# o_clone_rev_a.net
KiCad netlist of a schematic drawn in EAGLE
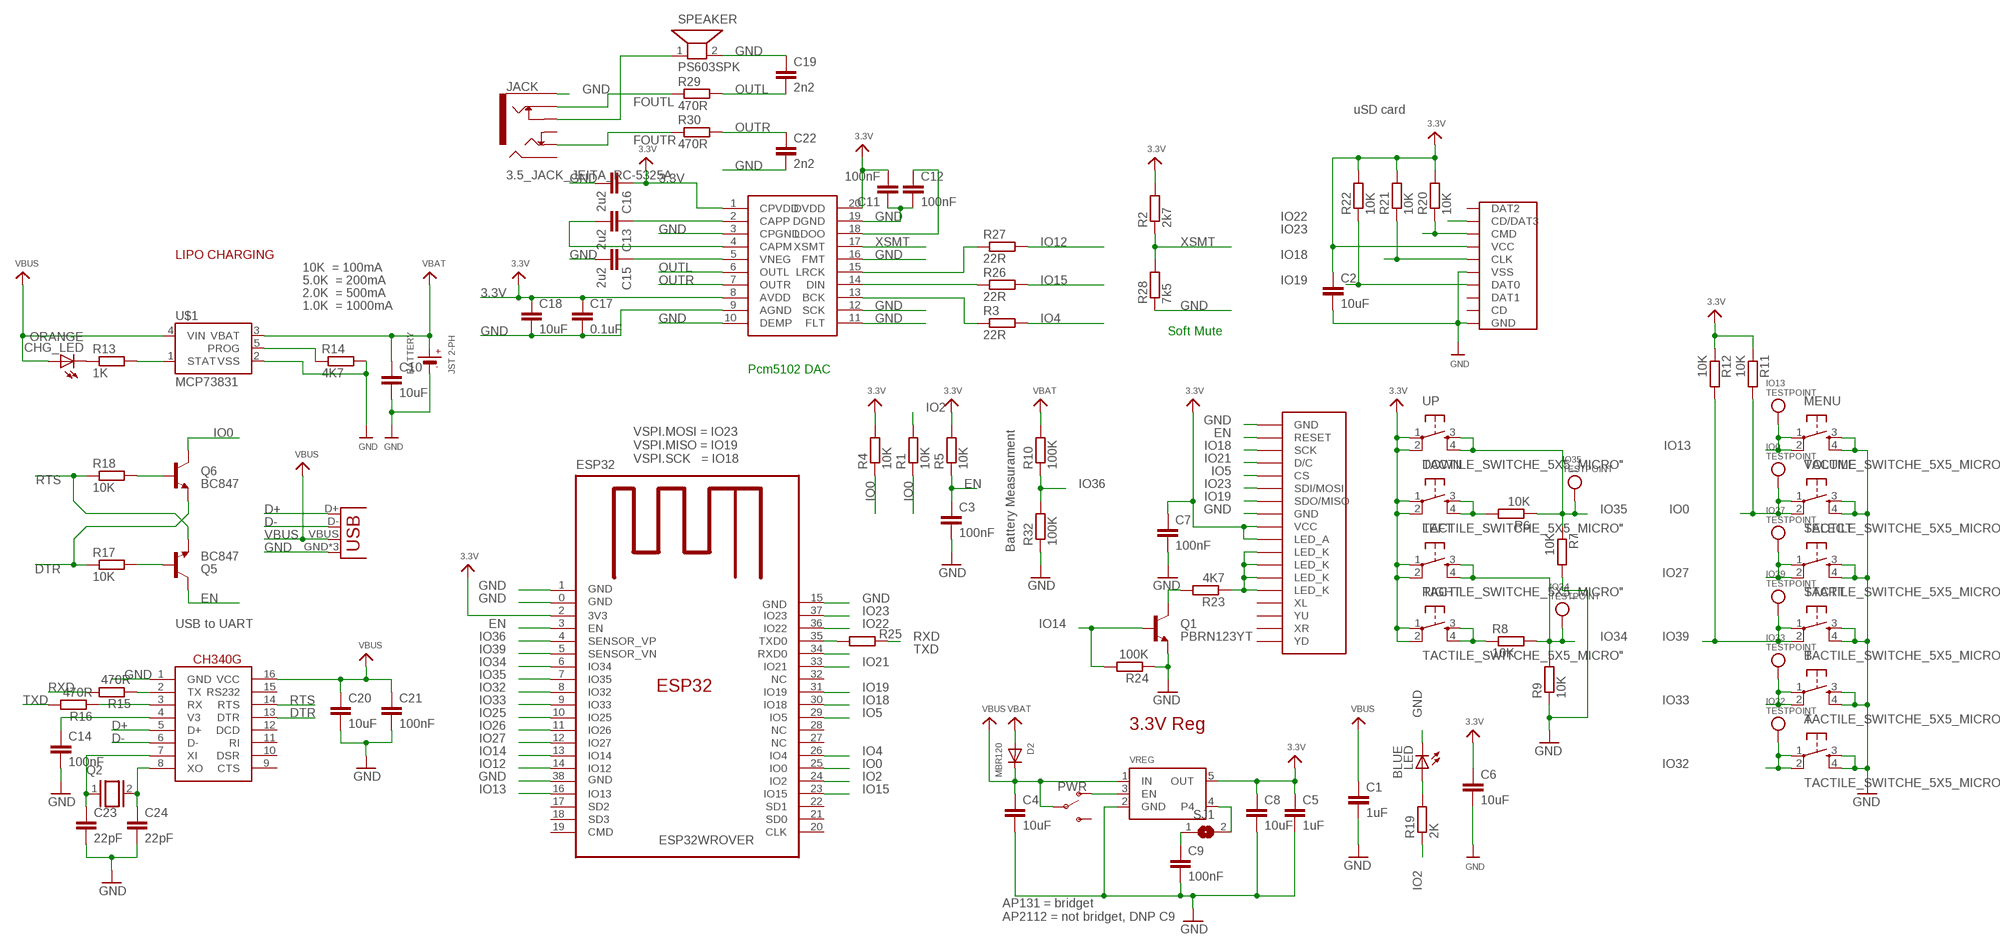
[diagram p0: schematic, sheet 1]

(export (version "E")
  (design (tool "Eeschema 10.0.6"))
  (components
    (comp (ref "A")
      (value "TACTILE_SWITCHE_5X5_MICRO\"")
      (footprint "eagle-import:TACTILE_SWITCH_5X5_MICRO")
      (libsource (lib "eagle-import") (part "TACTILE_SWITCHE_5X5_MICRO{dblquote}"))
    )
    (comp (ref "B")
      (value "TACTILE_SWITCHE_5X5_MICRO\"")
      (footprint "eagle-import:TACTILE_SWITCH_5X5_MICRO")
      (libsource (lib "eagle-import") (part "TACTILE_SWITCHE_5X5_MICRO{dblquote}"))
    )
    (comp (ref "BATTERY")
      (value "JST 2-PH")
      (footprint "eagle-import:JSTPH2")
      (libsource (lib "eagle-import") (part "JST_CONNECTOR"))
    )
    (comp (ref "C1")
      (value "1uF")
      (footprint "eagle-import:C0805")
      (libsource (lib "eagle-import") (part "C-EUC0805"))
    )
    (comp (ref "C2")
      (value "10uF")
      (footprint "eagle-import:C0805")
      (libsource (lib "eagle-import") (part "C-EUC0805"))
    )
    (comp (ref "C3")
      (value "100nF")
      (footprint "eagle-import:C0805")
      (libsource (lib "eagle-import") (part "C-EUC0805"))
    )
    (comp (ref "C4")
      (value "10uF")
      (footprint "eagle-import:C0805")
      (libsource (lib "eagle-import") (part "C-EUC0805"))
    )
    (comp (ref "C5")
      (value "1uF")
      (footprint "eagle-import:C0805")
      (libsource (lib "eagle-import") (part "C-EUC0805"))
    )
    (comp (ref "C6")
      (value "10uF")
      (footprint "eagle-import:C0805")
      (libsource (lib "eagle-import") (part "C-EUC0805"))
    )
    (comp (ref "C7")
      (value "100nF")
      (footprint "eagle-import:C0805")
      (libsource (lib "eagle-import") (part "C-EUC0805"))
    )
    (comp (ref "C8")
      (value "10uF")
      (footprint "eagle-import:C0805")
      (libsource (lib "eagle-import") (part "C-EUC0805"))
    )
    (comp (ref "C9")
      (value "100nF")
      (footprint "eagle-import:C0805")
      (libsource (lib "eagle-import") (part "C-EUC0805"))
    )
    (comp (ref "C10")
      (value "10uF")
      (footprint "eagle-import:C0805")
      (libsource (lib "eagle-import") (part "C-EUC0805"))
    )
    (comp (ref "C11")
      (value "100nF")
      (footprint "eagle-import:C0805")
      (libsource (lib "eagle-import") (part "C-EUC0805"))
    )
    (comp (ref "C12")
      (value "100nF")
      (footprint "eagle-import:C0805")
      (libsource (lib "eagle-import") (part "C-EUC0805"))
    )
    (comp (ref "C13")
      (value "2u2")
      (footprint "eagle-import:C0805")
      (libsource (lib "eagle-import") (part "C-EUC0805"))
    )
    (comp (ref "C14")
      (value "100nF")
      (footprint "eagle-import:C0805")
      (libsource (lib "eagle-import") (part "C-EUC0805"))
    )
    (comp (ref "C15")
      (value "2u2")
      (footprint "eagle-import:C0805")
      (libsource (lib "eagle-import") (part "C-EUC0805"))
    )
    (comp (ref "C16")
      (value "2u2")
      (footprint "eagle-import:C0805")
      (libsource (lib "eagle-import") (part "C-EUC0805"))
    )
    (comp (ref "C17")
      (value "0.1uF")
      (footprint "eagle-import:C0805")
      (libsource (lib "eagle-import") (part "C-EUC0805"))
    )
    (comp (ref "C18")
      (value "10uF")
      (footprint "eagle-import:C0805")
      (libsource (lib "eagle-import") (part "C-EUC0805"))
    )
    (comp (ref "C19")
      (value "2n2")
      (footprint "eagle-import:C0805")
      (libsource (lib "eagle-import") (part "C-EUC0805"))
    )
    (comp (ref "C20")
      (value "10uF")
      (footprint "eagle-import:C0805")
      (libsource (lib "eagle-import") (part "C-EUC0805"))
    )
    (comp (ref "C21")
      (value "100nF")
      (footprint "eagle-import:C0805")
      (libsource (lib "eagle-import") (part "C-EUC0805"))
    )
    (comp (ref "C22")
      (value "2n2")
      (footprint "eagle-import:C0805")
      (libsource (lib "eagle-import") (part "C-EUC0805"))
    )
    (comp (ref "C23")
      (value "22pF")
      (footprint "eagle-import:C0805")
      (libsource (lib "eagle-import") (part "C-EUC0805"))
    )
    (comp (ref "C24")
      (value "22pF")
      (footprint "eagle-import:C0805")
      (libsource (lib "eagle-import") (part "C-EUC0805"))
    )
    (comp (ref "CHG_LED")
      (value "ORANGE")
      (footprint "eagle-import:CHIPLED_0805")
      (libsource (lib "eagle-import") (part "LEDCHIPLED_0805"))
    )
    (comp (ref "D2")
      (value "MBR120")
      (footprint "eagle-import:SOD-123")
      (libsource (lib "eagle-import") (part "DIODESOD-123"))
    )
    (comp (ref "DOWN")
      (value "TACTILE_SWITCHE_5X5_MICRO\"")
      (footprint "eagle-import:TACTILE_SWITCH_5X5_MICRO")
      (libsource (lib "eagle-import") (part "TACTILE_SWITCHE_5X5_MICRO{dblquote}"))
    )
    (comp (ref "ESP32")
      (value "ESP32WROVER")
      (footprint "eagle-import:ESP32WROVER")
      (libsource (lib "eagle-import") (part "ESP32WROVER"))
    )
    (comp (ref "IO0")
      (value "TESTPOINT")
      (footprint "eagle-import:TESTPOINT")
      (libsource (lib "eagle-import") (part "TESTPOINT"))
    )
    (comp (ref "IO13")
      (value "TESTPOINT")
      (footprint "eagle-import:TESTPOINT")
      (libsource (lib "eagle-import") (part "TESTPOINT"))
    )
    (comp (ref "IO27")
      (value "TESTPOINT")
      (footprint "eagle-import:TESTPOINT")
      (libsource (lib "eagle-import") (part "TESTPOINT"))
    )
    (comp (ref "IO32")
      (value "TESTPOINT")
      (footprint "eagle-import:TESTPOINT")
      (libsource (lib "eagle-import") (part "TESTPOINT"))
    )
    (comp (ref "IO33")
      (value "TESTPOINT")
      (footprint "eagle-import:TESTPOINT")
      (libsource (lib "eagle-import") (part "TESTPOINT"))
    )
    (comp (ref "IO34")
      (value "TESTPOINT")
      (footprint "eagle-import:TESTPOINT")
      (libsource (lib "eagle-import") (part "TESTPOINT"))
    )
    (comp (ref "IO35")
      (value "TESTPOINT")
      (footprint "eagle-import:TESTPOINT")
      (libsource (lib "eagle-import") (part "TESTPOINT"))
    )
    (comp (ref "IO39")
      (value "TESTPOINT")
      (footprint "eagle-import:TESTPOINT")
      (libsource (lib "eagle-import") (part "TESTPOINT"))
    )
    (comp (ref "JACK")
      (value "3.5_JACK_JEITA_RC-5325A")
      (footprint "eagle-import:3.5_JACK_JEITA_RC-5325A")
      (libsource (lib "eagle-import") (part "3.5_JACK_JEITA_RC-5325A"))
    )
    (comp (ref "LCD")
      (value "ILI9341_3.2LCD_")
      (footprint "eagle-import:LI9341_3.2LCD")
      (libsource (lib "eagle-import") (part "ILI9341_3.2LCD_"))
    )
    (comp (ref "LED")
      (value "BLUE")
      (footprint "eagle-import:CHIPLED_0805")
      (libsource (lib "eagle-import") (part "LEDCHIPLED_0805"))
    )
    (comp (ref "LEFT")
      (value "TACTILE_SWITCHE_5X5_MICRO\"")
      (footprint "eagle-import:TACTILE_SWITCH_5X5_MICRO")
      (libsource (lib "eagle-import") (part "TACTILE_SWITCHE_5X5_MICRO{dblquote}"))
    )
    (comp (ref "MENU")
      (value "TACTILE_SWITCHE_5X5_MICRO\"")
      (footprint "eagle-import:TACTILE_SWITCH_5X5_MICRO")
      (libsource (lib "eagle-import") (part "TACTILE_SWITCHE_5X5_MICRO{dblquote}"))
    )
    (comp (ref "PCM5102")
      (value "PCM5102")
      (footprint "eagle-import:TSSOP20")
      (libsource (lib "eagle-import") (part "PCM5102"))
    )
    (comp (ref "PWR")
      (value "SWITCH-SPDT-SMD-RIGHT-ANGLE")
      (footprint "eagle-import:SWITCH_SPST_SMD_A")
      (libsource (lib "eagle-import") (part "SWITCH-SPDT-SMD-RIGHT-ANGLE"))
    )
    (comp (ref "Q1")
      (value "PBRN123YT")
      (footprint "eagle-import:SOT23-3")
      (libsource (lib "eagle-import") (part "TRANSISTOR_NPNSOT23-3"))
    )
    (comp (ref "Q2")
      (value "XTAL/S")
      (footprint "eagle-import:QS")
      (libsource (lib "eagle-import") (part "XTAL/S"))
    )
    (comp (ref "Q5")
      (value "BC847")
      (footprint "eagle-import:SOT23-3")
      (libsource (lib "eagle-import") (part "TRANSISTOR_NPNSOT23-3"))
    )
    (comp (ref "Q6")
      (value "BC847")
      (footprint "eagle-import:SOT23-3")
      (libsource (lib "eagle-import") (part "TRANSISTOR_NPNSOT23-3"))
    )
    (comp (ref "R1")
      (value "10K")
      (footprint "eagle-import:R0805")
      (libsource (lib "eagle-import") (part "R-EU_R0805"))
    )
    (comp (ref "R2")
      (value "2k7")
      (footprint "eagle-import:R0805")
      (libsource (lib "eagle-import") (part "R-EU_R0805"))
    )
    (comp (ref "R3")
      (value "22R")
      (footprint "eagle-import:R0805")
      (libsource (lib "eagle-import") (part "R-EU_R0805"))
    )
    (comp (ref "R4")
      (value "10K")
      (footprint "eagle-import:R0805")
      (libsource (lib "eagle-import") (part "R-EU_R0805"))
    )
    (comp (ref "R5")
      (value "10K")
      (footprint "eagle-import:R0805")
      (libsource (lib "eagle-import") (part "R-EU_R0805"))
    )
    (comp (ref "R6")
      (value "10K")
      (footprint "eagle-import:R0805")
      (libsource (lib "eagle-import") (part "R-EU_R0805"))
    )
    (comp (ref "R7")
      (value "10K")
      (footprint "eagle-import:R0805")
      (libsource (lib "eagle-import") (part "R-EU_R0805"))
    )
    (comp (ref "R8")
      (value "10K")
      (footprint "eagle-import:R0805")
      (libsource (lib "eagle-import") (part "R-EU_R0805"))
    )
    (comp (ref "R9")
      (value "10K")
      (footprint "eagle-import:R0805")
      (libsource (lib "eagle-import") (part "R-EU_R0805"))
    )
    (comp (ref "R10")
      (value "100K")
      (footprint "eagle-import:R0805")
      (libsource (lib "eagle-import") (part "R-EU_R0805"))
    )
    (comp (ref "R11")
      (value "10K")
      (footprint "eagle-import:R0805")
      (libsource (lib "eagle-import") (part "R-EU_R0805"))
    )
    (comp (ref "R12")
      (value "10K")
      (footprint "eagle-import:R0805")
      (libsource (lib "eagle-import") (part "R-EU_R0805"))
    )
    (comp (ref "R13")
      (value "1K")
      (footprint "eagle-import:R0805")
      (libsource (lib "eagle-import") (part "R-EU_R0805"))
    )
    (comp (ref "R14")
      (value "4K7")
      (footprint "eagle-import:R0805")
      (libsource (lib "eagle-import") (part "R-EU_R0805"))
    )
    (comp (ref "R15")
      (value "470R")
      (footprint "eagle-import:R0805")
      (libsource (lib "eagle-import") (part "R-EU_R0805"))
    )
    (comp (ref "R16")
      (value "470R")
      (footprint "eagle-import:R0805")
      (libsource (lib "eagle-import") (part "R-EU_R0805"))
    )
    (comp (ref "R17")
      (value "10K")
      (footprint "eagle-import:R0805")
      (libsource (lib "eagle-import") (part "R-EU_R0805"))
    )
    (comp (ref "R18")
      (value "10K")
      (footprint "eagle-import:R0805")
      (libsource (lib "eagle-import") (part "R-EU_R0805"))
    )
    (comp (ref "R19")
      (value "2K")
      (footprint "eagle-import:R0805")
      (libsource (lib "eagle-import") (part "R-EU_R0805"))
    )
    (comp (ref "R20")
      (value "10K")
      (footprint "eagle-import:R0805")
      (libsource (lib "eagle-import") (part "R-EU_R0805"))
    )
    (comp (ref "R21")
      (value "10K")
      (footprint "eagle-import:R0805")
      (libsource (lib "eagle-import") (part "R-EU_R0805"))
    )
    (comp (ref "R22")
      (value "10K")
      (footprint "eagle-import:R0805")
      (libsource (lib "eagle-import") (part "R-EU_R0805"))
    )
    (comp (ref "R23")
      (value "4K7")
      (footprint "eagle-import:R0805")
      (libsource (lib "eagle-import") (part "R-EU_R0805"))
    )
    (comp (ref "R24")
      (value "100K")
      (footprint "eagle-import:R0805")
      (libsource (lib "eagle-import") (part "R-EU_R0805"))
    )
    (comp (ref "R25")
      (value "470R")
      (footprint "eagle-import:R0805")
      (libsource (lib "eagle-import") (part "R-EU_R0805"))
    )
    (comp (ref "R26")
      (value "22R")
      (footprint "eagle-import:R0805")
      (libsource (lib "eagle-import") (part "R-EU_R0805"))
    )
    (comp (ref "R27")
      (value "22R")
      (footprint "eagle-import:R0805")
      (libsource (lib "eagle-import") (part "R-EU_R0805"))
    )
    (comp (ref "R28")
      (value "7k5")
      (footprint "eagle-import:R0805")
      (libsource (lib "eagle-import") (part "R-EU_R0805"))
    )
    (comp (ref "R29")
      (value "470R")
      (footprint "eagle-import:R0805")
      (libsource (lib "eagle-import") (part "R-EU_R0805"))
    )
    (comp (ref "R30")
      (value "470R")
      (footprint "eagle-import:R0805")
      (libsource (lib "eagle-import") (part "R-EU_R0805"))
    )
    (comp (ref "R32")
      (value "100K")
      (footprint "eagle-import:R0805")
      (libsource (lib "eagle-import") (part "R-EU_R0805"))
    )
    (comp (ref "RIGHT")
      (value "TACTILE_SWITCHE_5X5_MICRO\"")
      (footprint "eagle-import:TACTILE_SWITCH_5X5_MICRO")
      (libsource (lib "eagle-import") (part "TACTILE_SWITCHE_5X5_MICRO{dblquote}"))
    )
    (comp (ref "SD_CARD")
      (value "MICRO_SD_CARD\"")
      (footprint "eagle-import:TFP09-2--12B")
      (libsource (lib "eagle-import") (part "MICRO_SD_CARD{dblquote}"))
    )
    (comp (ref "SELECT")
      (value "TACTILE_SWITCHE_5X5_MICRO\"")
      (footprint "eagle-import:TACTILE_SWITCH_5X5_MICRO")
      (libsource (lib "eagle-import") (part "TACTILE_SWITCHE_5X5_MICRO{dblquote}"))
    )
    (comp (ref "SJ1") (value "SJ") (footprint "eagle-import:SJ") (libsource (lib "eagle-import") (part "SJ")))
    (comp (ref "SPEAKER")
      (value "PS603SPK")
      (footprint "eagle-import:PS603")
      (libsource (lib "eagle-import") (part "PS603SPK"))
    )
    (comp (ref "START")
      (value "TACTILE_SWITCHE_5X5_MICRO\"")
      (footprint "eagle-import:TACTILE_SWITCH_5X5_MICRO")
      (libsource (lib "eagle-import") (part "TACTILE_SWITCHE_5X5_MICRO{dblquote}"))
    )
    (comp (ref "U$1")
      (value "MCP73831")
      (footprint "eagle-import:SOT95P290X120-5")
      (libsource (lib "eagle-import") (part "MCP73831"))
    )
    (comp (ref "U$23")
      (value "CH340G")
      (footprint "eagle-import:SO16")
      (libsource (lib "eagle-import") (part "CH340G"))
    )
    (comp (ref "UP")
      (value "TACTILE_SWITCHE_5X5_MICRO\"")
      (footprint "eagle-import:TACTILE_SWITCH_5X5_MICRO")
      (libsource (lib "eagle-import") (part "TACTILE_SWITCHE_5X5_MICRO{dblquote}"))
    )
    (comp (ref "USB")
      (value "USB_MICRO_ATTEND_")
      (footprint "eagle-import:USB_MICRO")
      (libsource (lib "eagle-import") (part "USB_MICRO_ATTEND_"))
    )
    (comp (ref "VOLUME")
      (value "TACTILE_SWITCHE_5X5_MICRO\"")
      (footprint "eagle-import:TACTILE_SWITCH_5X5_MICRO")
      (libsource (lib "eagle-import") (part "TACTILE_SWITCHE_5X5_MICRO{dblquote}"))
    )
    (comp (ref "VREG")
      (value "AP2112K-3.3_")
      (footprint "eagle-import:SOT95P290X120-5")
      (libsource (lib "eagle-import") (part "AP2112K-3.3_"))
    )
  )
  (nets
    (net (code "1") (name "/D+") (class "Default")
      (node (ref "U$23") (pin "5") (pinfunction "D+_5") (pintype "bidirectional"))
      (node (ref "USB") (pin "D+") (pinfunction "D+_D+") (pintype "bidirectional"))
    )
    (net (code "2") (name "/D-") (class "Default")
      (node (ref "U$23") (pin "6") (pinfunction "D-_6") (pintype "bidirectional"))
      (node (ref "USB") (pin "D-") (pinfunction "D-_D-") (pintype "bidirectional"))
    )
    (net (code "3") (name "/DTR") (class "Default")
      (node (ref "Q6") (pin "2") (pinfunction "E_2") (pintype "passive"))
      (node (ref "R17") (pin "1") (pinfunction "1_1") (pintype "passive"))
      (node (ref "U$23") (pin "13") (pinfunction "DTR_13") (pintype "bidirectional"))
    )
    (net (code "4") (name "/EN") (class "Default")
      (node (ref "C3") (pin "1") (pinfunction "1_1") (pintype "passive"))
      (node (ref "ESP32") (pin "3") (pinfunction "EN_3") (pintype "bidirectional"))
      (node (ref "LCD") (pin "P$2") (pinfunction "RESET_P$2") (pintype "bidirectional"))
      (node (ref "Q5") (pin "3") (pinfunction "C_3") (pintype "passive"))
      (node (ref "R5") (pin "1") (pinfunction "1_1") (pintype "passive"))
    )
    (net (code "5") (name "/FOUTL") (class "Default")
      (node (ref "JACK") (pin "5") (pinfunction "5_5") (pintype "bidirectional"))
      (node (ref "R29") (pin "1") (pinfunction "1_1") (pintype "passive"))
    )
    (net (code "6") (name "/FOUTR") (class "Default")
      (node (ref "JACK") (pin "3") (pinfunction "3_3") (pintype "bidirectional"))
      (node (ref "R30") (pin "1") (pinfunction "1_1") (pintype "passive"))
    )
    (net (code "7") (name "/IO0") (class "Default")
      (node (ref "ESP32") (pin "25") (pinfunction "IO0_25") (pintype "bidirectional"))
      (node (ref "IO0") (pin "P$1") (pinfunction "P$1_P$1") (pintype "bidirectional"))
      (node (ref "Q6") (pin "3") (pinfunction "C_3") (pintype "passive"))
      (node (ref "R1") (pin "1") (pinfunction "1_1") (pintype "passive"))
      (node (ref "R11") (pin "2") (pinfunction "2_2") (pintype "passive"))
      (node (ref "R4") (pin "1") (pinfunction "1_1") (pintype "passive"))
      (node (ref "VOLUME") (pin "1") (pinfunction "1_1") (pintype "passive"))
      (node (ref "VOLUME") (pin "2") (pinfunction "2_2") (pintype "passive"))
    )
    (net (code "8") (name "/IO2") (class "Default")
      (node (ref "ESP32") (pin "24") (pinfunction "IO2_24") (pintype "bidirectional"))
      (node (ref "R1") (pin "2") (pinfunction "2_2") (pintype "passive"))
      (node (ref "R19") (pin "1") (pinfunction "1_1") (pintype "passive"))
    )
    (net (code "9") (name "/IO4") (class "Default")
      (node (ref "ESP32") (pin "26") (pinfunction "IO4_26") (pintype "bidirectional"))
      (node (ref "R3") (pin "2") (pinfunction "2_2") (pintype "passive"))
    )
    (net (code "10") (name "/IO5") (class "Default")
      (node (ref "ESP32") (pin "29") (pinfunction "IO5_29") (pintype "bidirectional"))
      (node (ref "LCD") (pin "P$5") (pinfunction "CS_P$5") (pintype "bidirectional"))
    )
    (net (code "11") (name "/IO12") (class "Default")
      (node (ref "ESP32") (pin "14") (pinfunction "IO12_14") (pintype "bidirectional"))
      (node (ref "R27") (pin "2") (pinfunction "2_2") (pintype "passive"))
    )
    (net (code "12") (name "/IO13") (class "Default")
      (node (ref "ESP32") (pin "16") (pinfunction "IO13_16") (pintype "bidirectional"))
      (node (ref "IO13") (pin "P$1") (pinfunction "P$1_P$1") (pintype "bidirectional"))
      (node (ref "MENU") (pin "1") (pinfunction "1_1") (pintype "passive"))
      (node (ref "MENU") (pin "2") (pinfunction "2_2") (pintype "passive"))
    )
    (net (code "13") (name "/IO14") (class "Default")
      (node (ref "ESP32") (pin "13") (pinfunction "IO14_13") (pintype "bidirectional"))
      (node (ref "Q1") (pin "1") (pinfunction "B_1") (pintype "passive"))
      (node (ref "R24") (pin "2") (pinfunction "2_2") (pintype "passive"))
    )
    (net (code "14") (name "/IO15") (class "Default")
      (node (ref "ESP32") (pin "23") (pinfunction "IO15_23") (pintype "bidirectional"))
      (node (ref "R26") (pin "2") (pinfunction "2_2") (pintype "passive"))
    )
    (net (code "15") (name "/IO18") (class "Default")
      (node (ref "ESP32") (pin "30") (pinfunction "IO18_30") (pintype "bidirectional"))
      (node (ref "LCD") (pin "P$3") (pinfunction "SCK_P$3") (pintype "bidirectional"))
      (node (ref "R21") (pin "1") (pinfunction "1_1") (pintype "passive"))
      (node (ref "SD_CARD") (pin "CLK") (pinfunction "CLK_CLK") (pintype "bidirectional"))
    )
    (net (code "16") (name "/IO19") (class "Default")
      (node (ref "ESP32") (pin "31") (pinfunction "IO19_31") (pintype "bidirectional"))
      (node (ref "LCD") (pin "P$7") (pinfunction "SDO/MISO_P$7") (pintype "bidirectional"))
      (node (ref "R22") (pin "1") (pinfunction "1_1") (pintype "passive"))
      (node (ref "SD_CARD") (pin "DAT0") (pinfunction "DAT0_DAT0") (pintype "bidirectional"))
    )
    (net (code "17") (name "/IO21") (class "Default")
      (node (ref "ESP32") (pin "33") (pinfunction "IO21_33") (pintype "bidirectional"))
      (node (ref "LCD") (pin "P$4") (pinfunction "D/C_P$4") (pintype "bidirectional"))
    )
    (net (code "18") (name "/IO22") (class "Default")
      (node (ref "ESP32") (pin "36") (pinfunction "IO22_36") (pintype "bidirectional"))
      (node (ref "SD_CARD") (pin "CD/DAT3") (pinfunction "CD/DAT3_CD/DAT3") (pintype "bidirectional"))
    )
    (net (code "19") (name "/IO23") (class "Default")
      (node (ref "ESP32") (pin "37") (pinfunction "IO23_37") (pintype "bidirectional"))
      (node (ref "LCD") (pin "P$6") (pinfunction "SDI/MOSI_P$6") (pintype "bidirectional"))
      (node (ref "R20") (pin "1") (pinfunction "1_1") (pintype "passive"))
      (node (ref "SD_CARD") (pin "CMD") (pinfunction "CMD_CMD") (pintype "bidirectional"))
    )
    (net (code "20") (name "/IO25") (class "Default")
      (node (ref "ESP32") (pin "10") (pinfunction "IO25_10") (pintype "bidirectional"))
    )
    (net (code "21") (name "/IO26") (class "Default")
      (node (ref "ESP32") (pin "11") (pinfunction "IO26_11") (pintype "bidirectional"))
    )
    (net (code "22") (name "/IO27") (class "Default")
      (node (ref "ESP32") (pin "12") (pinfunction "IO27_12") (pintype "bidirectional"))
      (node (ref "IO27") (pin "P$1") (pinfunction "P$1_P$1") (pintype "bidirectional"))
      (node (ref "SELECT") (pin "1") (pinfunction "1_1") (pintype "passive"))
      (node (ref "SELECT") (pin "2") (pinfunction "2_2") (pintype "passive"))
    )
    (net (code "23") (name "/IO32") (class "Default")
      (node (ref "A") (pin "1") (pinfunction "1_1") (pintype "passive"))
      (node (ref "A") (pin "2") (pinfunction "2_2") (pintype "passive"))
      (node (ref "ESP32") (pin "8") (pinfunction "IO32_8") (pintype "bidirectional"))
      (node (ref "IO32") (pin "P$1") (pinfunction "P$1_P$1") (pintype "bidirectional"))
    )
    (net (code "24") (name "/IO33") (class "Default")
      (node (ref "B") (pin "1") (pinfunction "1_1") (pintype "passive"))
      (node (ref "B") (pin "2") (pinfunction "2_2") (pintype "passive"))
      (node (ref "ESP32") (pin "9") (pinfunction "IO33_9") (pintype "bidirectional"))
      (node (ref "IO33") (pin "P$1") (pinfunction "P$1_P$1") (pintype "bidirectional"))
    )
    (net (code "25") (name "/IO34") (class "Default")
      (node (ref "ESP32") (pin "6") (pinfunction "IO34_6") (pintype "bidirectional"))
      (node (ref "IO34") (pin "P$1") (pinfunction "P$1_P$1") (pintype "bidirectional"))
      (node (ref "LEFT") (pin "3") (pinfunction "3_3") (pintype "passive"))
      (node (ref "LEFT") (pin "4") (pinfunction "4_4") (pintype "passive"))
      (node (ref "R8") (pin "2") (pinfunction "2_2") (pintype "passive"))
      (node (ref "R9") (pin "2") (pinfunction "2_2") (pintype "passive"))
    )
    (net (code "26") (name "/IO35") (class "Default")
      (node (ref "ESP32") (pin "7") (pinfunction "IO35_7") (pintype "bidirectional"))
      (node (ref "IO35") (pin "P$1") (pinfunction "P$1_P$1") (pintype "bidirectional"))
      (node (ref "R6") (pin "1") (pinfunction "1_1") (pintype "passive"))
      (node (ref "R7") (pin "1") (pinfunction "1_1") (pintype "passive"))
      (node (ref "UP") (pin "3") (pinfunction "3_3") (pintype "passive"))
      (node (ref "UP") (pin "4") (pinfunction "4_4") (pintype "passive"))
    )
    (net (code "27") (name "/IO36") (class "Default")
      (node (ref "ESP32") (pin "4") (pinfunction "SENSOR_VP_4") (pintype "bidirectional"))
      (node (ref "R10") (pin "1") (pinfunction "1_1") (pintype "passive"))
      (node (ref "R32") (pin "2") (pinfunction "2_2") (pintype "passive"))
    )
    (net (code "28") (name "/IO39") (class "Default")
      (node (ref "ESP32") (pin "5") (pinfunction "SENSOR_VN_5") (pintype "bidirectional"))
      (node (ref "IO39") (pin "P$1") (pinfunction "P$1_P$1") (pintype "bidirectional"))
      (node (ref "R12") (pin "2") (pinfunction "2_2") (pintype "passive"))
      (node (ref "START") (pin "1") (pinfunction "1_1") (pintype "passive"))
      (node (ref "START") (pin "2") (pinfunction "2_2") (pintype "passive"))
    )
    (net (code "29") (name "/OUTL") (class "Default")
      (node (ref "C19") (pin "2") (pinfunction "2_2") (pintype "passive"))
      (node (ref "PCM5102") (pin "6") (pinfunction "OUTL_6") (pintype "bidirectional"))
      (node (ref "R29") (pin "2") (pinfunction "2_2") (pintype "passive"))
    )
    (net (code "30") (name "/OUTR") (class "Default")
      (node (ref "C22") (pin "1") (pinfunction "1_1") (pintype "passive"))
      (node (ref "PCM5102") (pin "7") (pinfunction "OUTR_7") (pintype "bidirectional"))
      (node (ref "R30") (pin "2") (pinfunction "2_2") (pintype "passive"))
    )
    (net (code "31") (name "/RTS") (class "Default")
      (node (ref "Q5") (pin "2") (pinfunction "E_2") (pintype "passive"))
      (node (ref "R18") (pin "1") (pinfunction "1_1") (pintype "passive"))
      (node (ref "U$23") (pin "14") (pinfunction "RTS_14") (pintype "bidirectional"))
    )
    (net (code "32") (name "/RXD") (class "Default")
      (node (ref "R15") (pin "2") (pinfunction "2_2") (pintype "passive"))
      (node (ref "R25") (pin "1") (pinfunction "1_1") (pintype "passive"))
    )
    (net (code "33") (name "/TXD") (class "Default")
      (node (ref "ESP32") (pin "34") (pinfunction "RXD0_34") (pintype "bidirectional"))
      (node (ref "R16") (pin "2") (pinfunction "2_2") (pintype "passive"))
    )
    (net (code "34") (name "/XSMT") (class "Default")
      (node (ref "PCM5102") (pin "17") (pinfunction "XSMT_17") (pintype "bidirectional"))
      (node (ref "R2") (pin "1") (pinfunction "1_1") (pintype "passive"))
      (node (ref "R28") (pin "2") (pinfunction "2_2") (pintype "passive"))
    )
    (net (code "35") (name "3.3V") (class "Default")
      (node (ref "C11") (pin "2") (pinfunction "2_2") (pintype "passive"))
      (node (ref "C16") (pin "1") (pinfunction "1_1") (pintype "passive"))
      (node (ref "C17") (pin "1") (pinfunction "1_1") (pintype "passive"))
      (node (ref "C18") (pin "1") (pinfunction "1_1") (pintype "passive"))
      (node (ref "C2") (pin "1") (pinfunction "1_1") (pintype "passive"))
      (node (ref "C5") (pin "1") (pinfunction "1_1") (pintype "passive"))
      (node (ref "C6") (pin "1") (pinfunction "1_1") (pintype "passive"))
      (node (ref "C7") (pin "1") (pinfunction "1_1") (pintype "passive"))
      (node (ref "C8") (pin "1") (pinfunction "1_1") (pintype "passive"))
      (node (ref "DOWN") (pin "1") (pinfunction "1_1") (pintype "passive"))
      (node (ref "DOWN") (pin "2") (pinfunction "2_2") (pintype "passive"))
      (node (ref "ESP32") (pin "2") (pinfunction "3V3_2") (pintype "power_in"))
      (node (ref "LCD") (pin "P$10") (pinfunction "LED_A_P$10") (pintype "bidirectional"))
      (node (ref "LCD") (pin "P$9") (pinfunction "VCC_P$9") (pintype "bidirectional"))
      (node (ref "LEFT") (pin "1") (pinfunction "1_1") (pintype "passive"))
      (node (ref "LEFT") (pin "2") (pinfunction "2_2") (pintype "passive"))
      (node (ref "PCM5102") (pin "1") (pinfunction "CPVDD_1") (pintype "bidirectional"))
      (node (ref "PCM5102") (pin "20") (pinfunction "DVDD_20") (pintype "bidirectional"))
      (node (ref "PCM5102") (pin "8") (pinfunction "AVDD_8") (pintype "bidirectional"))
      (node (ref "R11") (pin "1") (pinfunction "1_1") (pintype "passive"))
      (node (ref "R12") (pin "1") (pinfunction "1_1") (pintype "passive"))
      (node (ref "R2") (pin "2") (pinfunction "2_2") (pintype "passive"))
      (node (ref "R20") (pin "2") (pinfunction "2_2") (pintype "passive"))
      (node (ref "R21") (pin "2") (pinfunction "2_2") (pintype "passive"))
      (node (ref "R22") (pin "2") (pinfunction "2_2") (pintype "passive"))
      (node (ref "R4") (pin "2") (pinfunction "2_2") (pintype "passive"))
      (node (ref "R5") (pin "2") (pinfunction "2_2") (pintype "passive"))
      (node (ref "RIGHT") (pin "1") (pinfunction "1_1") (pintype "passive"))
      (node (ref "RIGHT") (pin "2") (pinfunction "2_2") (pintype "passive"))
      (node (ref "SD_CARD") (pin "VCC") (pinfunction "VCC_VCC") (pintype "bidirectional"))
      (node (ref "UP") (pin "1") (pinfunction "1_1") (pintype "passive"))
      (node (ref "UP") (pin "2") (pinfunction "2_2") (pintype "passive"))
      (node (ref "VREG") (pin "5") (pinfunction "OUT_5") (pintype "bidirectional"))
    )
    (net (code "36") (name "GND") (class "Default")
      (node (ref "A") (pin "3") (pinfunction "3_3") (pintype "passive"))
      (node (ref "A") (pin "4") (pinfunction "4_4") (pintype "passive"))
      (node (ref "B") (pin "3") (pinfunction "3_3") (pintype "passive"))
      (node (ref "B") (pin "4") (pinfunction "4_4") (pintype "passive"))
      (node (ref "BATTERY") (pin "1") (pinfunction "-_1") (pintype "passive"))
      (node (ref "C1") (pin "2") (pinfunction "2_2") (pintype "passive"))
      (node (ref "C10") (pin "2") (pinfunction "2_2") (pintype "passive"))
      (node (ref "C11") (pin "1") (pinfunction "1_1") (pintype "passive"))
      (node (ref "C12") (pin "2") (pinfunction "2_2") (pintype "passive"))
      (node (ref "C14") (pin "2") (pinfunction "2_2") (pintype "passive"))
      (node (ref "C15") (pin "2") (pinfunction "2_2") (pintype "passive"))
      (node (ref "C16") (pin "2") (pinfunction "2_2") (pintype "passive"))
      (node (ref "C17") (pin "2") (pinfunction "2_2") (pintype "passive"))
      (node (ref "C18") (pin "2") (pinfunction "2_2") (pintype "passive"))
      (node (ref "C19") (pin "1") (pinfunction "1_1") (pintype "passive"))
      (node (ref "C2") (pin "2") (pinfunction "2_2") (pintype "passive"))
      (node (ref "C20") (pin "2") (pinfunction "2_2") (pintype "passive"))
      (node (ref "C21") (pin "2") (pinfunction "2_2") (pintype "passive"))
      (node (ref "C22") (pin "2") (pinfunction "2_2") (pintype "passive"))
      (node (ref "C23") (pin "2") (pinfunction "2_2") (pintype "passive"))
      (node (ref "C24") (pin "2") (pinfunction "2_2") (pintype "passive"))
      (node (ref "C3") (pin "2") (pinfunction "2_2") (pintype "passive"))
      (node (ref "C4") (pin "2") (pinfunction "2_2") (pintype "passive"))
      (node (ref "C5") (pin "2") (pinfunction "2_2") (pintype "passive"))
      (node (ref "C6") (pin "2") (pinfunction "2_2") (pintype "passive"))
      (node (ref "C7") (pin "2") (pinfunction "2_2") (pintype "passive"))
      (node (ref "C8") (pin "2") (pinfunction "2_2") (pintype "passive"))
      (node (ref "C9") (pin "2") (pinfunction "2_2") (pintype "passive"))
      (node (ref "ESP32") (pin "0") (pinfunction "GND_0") (pintype "power_in"))
      (node (ref "ESP32") (pin "1") (pinfunction "GND_1") (pintype "power_in"))
      (node (ref "ESP32") (pin "15") (pinfunction "GND_15") (pintype "power_in"))
      (node (ref "ESP32") (pin "38") (pinfunction "GND_38") (pintype "power_in"))
      (node (ref "JACK") (pin "1") (pinfunction "1_1") (pintype "bidirectional"))
      (node (ref "LCD") (pin "P$1") (pinfunction "GND_P$1") (pintype "bidirectional"))
      (node (ref "LCD") (pin "P$8") (pinfunction "GND_P$8") (pintype "bidirectional"))
      (node (ref "LED") (pin "C") (pinfunction "C_C") (pintype "passive"))
      (node (ref "MENU") (pin "3") (pinfunction "3_3") (pintype "passive"))
      (node (ref "MENU") (pin "4") (pinfunction "4_4") (pintype "passive"))
      (node (ref "PCM5102") (pin "10") (pinfunction "DEMP_10") (pintype "bidirectional"))
      (node (ref "PCM5102") (pin "11") (pinfunction "FLT_11") (pintype "bidirectional"))
      (node (ref "PCM5102") (pin "12") (pinfunction "SCK_12") (pintype "bidirectional"))
      (node (ref "PCM5102") (pin "16") (pinfunction "FMT_16") (pintype "bidirectional"))
      (node (ref "PCM5102") (pin "19") (pinfunction "DGND_19") (pintype "bidirectional"))
      (node (ref "PCM5102") (pin "3") (pinfunction "CPGND_3") (pintype "bidirectional"))
      (node (ref "PCM5102") (pin "9") (pinfunction "AGND_9") (pintype "bidirectional"))
      (node (ref "Q1") (pin "2") (pinfunction "E_2") (pintype "passive"))
      (node (ref "R14") (pin "2") (pinfunction "2_2") (pintype "passive"))
      (node (ref "R24") (pin "1") (pinfunction "1_1") (pintype "passive"))
      (node (ref "R28") (pin "1") (pinfunction "1_1") (pintype "passive"))
      (node (ref "R32") (pin "1") (pinfunction "1_1") (pintype "passive"))
      (node (ref "R7") (pin "2") (pinfunction "2_2") (pintype "passive"))
      (node (ref "R9") (pin "1") (pinfunction "1_1") (pintype "passive"))
      (node (ref "SD_CARD") (pin "GND") (pinfunction "GND_GND") (pintype "bidirectional"))
      (node (ref "SD_CARD") (pin "GND@1") (pinfunction "GND_GND@1") (pintype "bidirectional"))
      (node (ref "SD_CARD") (pin "GND@2") (pinfunction "GND_GND@2") (pintype "bidirectional"))
      (node (ref "SD_CARD") (pin "GND@3") (pinfunction "VSS_GND@3") (pintype "bidirectional"))
      (node (ref "SD_CARD") (pin "VSS") (pinfunction "GND_VSS") (pintype "bidirectional"))
      (node (ref "SELECT") (pin "3") (pinfunction "3_3") (pintype "passive"))
      (node (ref "SELECT") (pin "4") (pinfunction "4_4") (pintype "passive"))
      (node (ref "SPEAKER") (pin "2") (pinfunction "2_2") (pintype "passive"))
      (node (ref "START") (pin "3") (pinfunction "3_3") (pintype "passive"))
      (node (ref "START") (pin "4") (pinfunction "4_4") (pintype "passive"))
      (node (ref "U$1") (pin "2") (pinfunction "VSS_2") (pintype "power_in"))
      (node (ref "U$23") (pin "1") (pinfunction "GND_1") (pintype "bidirectional"))
      (node (ref "USB") (pin "GND") (pinfunction "GND_GND") (pintype "bidirectional"))
      (node (ref "USB") (pin "GND@2") (pinfunction "GND_GND@2") (pintype "bidirectional"))
      (node (ref "USB") (pin "GND@3") (pinfunction "GND_GND@3") (pintype "bidirectional"))
      (node (ref "VOLUME") (pin "3") (pinfunction "3_3") (pintype "passive"))
      (node (ref "VOLUME") (pin "4") (pinfunction "4_4") (pintype "passive"))
      (node (ref "VREG") (pin "2") (pinfunction "GND_2") (pintype "bidirectional"))
    )
    (net (code "37") (name "Net-(C9-Pad1)") (class "Default")
      (node (ref "C9") (pin "1") (pinfunction "1_1") (pintype "passive"))
      (node (ref "SJ1") (pin "1") (pinfunction "1_1") (pintype "passive"))
    )
    (net (code "38") (name "Net-(CHG_LED-PadC)") (class "Default")
      (node (ref "CHG_LED") (pin "C") (pinfunction "C_C") (pintype "passive"))
      (node (ref "R13") (pin "1") (pinfunction "1_1") (pintype "passive"))
    )
    (net (code "39") (name "Net-(DOWN-Pad3)") (class "Default")
      (node (ref "DOWN") (pin "3") (pinfunction "3_3") (pintype "passive"))
      (node (ref "DOWN") (pin "4") (pinfunction "4_4") (pintype "passive"))
      (node (ref "R6") (pin "2") (pinfunction "2_2") (pintype "passive"))
    )
    (net (code "40") (name "Net-(ESP32-TXD0)") (class "Default")
      (node (ref "ESP32") (pin "35") (pinfunction "TXD0_35") (pintype "bidirectional"))
      (node (ref "R25") (pin "2") (pinfunction "2_2") (pintype "passive"))
    )
    (net (code "41") (name "Net-(JACK-Pad6)") (class "Default")
      (node (ref "JACK") (pin "6") (pinfunction "6_6") (pintype "bidirectional"))
      (node (ref "SPEAKER") (pin "1") (pinfunction "1_1") (pintype "passive"))
    )
    (net (code "42") (name "Net-(LCD-LED_K-PadP$11)") (class "Default")
      (node (ref "LCD") (pin "P$11") (pinfunction "LED_K_P$11") (pintype "bidirectional"))
      (node (ref "LCD") (pin "P$12") (pinfunction "LED_K_P$12") (pintype "bidirectional"))
      (node (ref "LCD") (pin "P$13") (pinfunction "LED_K_P$13") (pintype "bidirectional"))
      (node (ref "LCD") (pin "P$14") (pinfunction "LED_K_P$14") (pintype "bidirectional"))
      (node (ref "R23") (pin "1") (pinfunction "1_1") (pintype "passive"))
    )
    (net (code "43") (name "Net-(LED-PadA)") (class "Default")
      (node (ref "LED") (pin "A") (pinfunction "A_A") (pintype "passive"))
      (node (ref "R19") (pin "2") (pinfunction "2_2") (pintype "passive"))
    )
    (net (code "44") (name "Net-(PCM5102-BCK)") (class "Default")
      (node (ref "PCM5102") (pin "13") (pinfunction "BCK_13") (pintype "bidirectional"))
      (node (ref "R3") (pin "1") (pinfunction "1_1") (pintype "passive"))
    )
    (net (code "45") (name "Net-(PCM5102-CAPM)") (class "Default")
      (node (ref "C13") (pin "2") (pinfunction "2_2") (pintype "passive"))
      (node (ref "PCM5102") (pin "4") (pinfunction "CAPM_4") (pintype "bidirectional"))
    )
    (net (code "46") (name "Net-(PCM5102-CAPP)") (class "Default")
      (node (ref "C13") (pin "1") (pinfunction "1_1") (pintype "passive"))
      (node (ref "PCM5102") (pin "2") (pinfunction "CAPP_2") (pintype "bidirectional"))
    )
    (net (code "47") (name "Net-(PCM5102-DIN)") (class "Default")
      (node (ref "PCM5102") (pin "14") (pinfunction "DIN_14") (pintype "bidirectional"))
      (node (ref "R26") (pin "1") (pinfunction "1_1") (pintype "passive"))
    )
    (net (code "48") (name "Net-(PCM5102-LDOO)") (class "Default")
      (node (ref "C12") (pin "1") (pinfunction "1_1") (pintype "passive"))
      (node (ref "PCM5102") (pin "18") (pinfunction "LDOO_18") (pintype "bidirectional"))
    )
    (net (code "49") (name "Net-(PCM5102-LRCK)") (class "Default")
      (node (ref "PCM5102") (pin "15") (pinfunction "LRCK_15") (pintype "bidirectional"))
      (node (ref "R27") (pin "1") (pinfunction "1_1") (pintype "passive"))
    )
    (net (code "50") (name "Net-(PCM5102-VNEG)") (class "Default")
      (node (ref "C15") (pin "1") (pinfunction "1_1") (pintype "passive"))
      (node (ref "PCM5102") (pin "5") (pinfunction "VNEG_5") (pintype "bidirectional"))
    )
    (net (code "51") (name "Net-(PWR-O)") (class "Default")
      (node (ref "PWR") (pin "1") (pinfunction "O_1") (pintype "passive"))
      (node (ref "VREG") (pin "3") (pinfunction "EN_3") (pintype "bidirectional"))
    )
    (net (code "52") (name "Net-(Q1-C)") (class "Default")
      (node (ref "Q1") (pin "3") (pinfunction "C_3") (pintype "passive"))
      (node (ref "R23") (pin "2") (pinfunction "2_2") (pintype "passive"))
    )
    (net (code "53") (name "Net-(Q5-B)") (class "Default")
      (node (ref "Q5") (pin "1") (pinfunction "B_1") (pintype "passive"))
      (node (ref "R17") (pin "2") (pinfunction "2_2") (pintype "passive"))
    )
    (net (code "54") (name "Net-(Q6-B)") (class "Default")
      (node (ref "Q6") (pin "1") (pinfunction "B_1") (pintype "passive"))
      (node (ref "R18") (pin "2") (pinfunction "2_2") (pintype "passive"))
    )
    (net (code "55") (name "Net-(R8-Pad1)") (class "Default")
      (node (ref "R8") (pin "1") (pinfunction "1_1") (pintype "passive"))
      (node (ref "RIGHT") (pin "3") (pinfunction "3_3") (pintype "passive"))
      (node (ref "RIGHT") (pin "4") (pinfunction "4_4") (pintype "passive"))
    )
    (net (code "56") (name "Net-(U$1-PROG)") (class "Default")
      (node (ref "R14") (pin "1") (pinfunction "1_1") (pintype "passive"))
      (node (ref "U$1") (pin "5") (pinfunction "PROG_5") (pintype "input"))
    )
    (net (code "57") (name "Net-(U$1-STAT)") (class "Default")
      (node (ref "R13") (pin "2") (pinfunction "2_2") (pintype "passive"))
      (node (ref "U$1") (pin "1") (pinfunction "STAT_1") (pintype "output"))
    )
    (net (code "58") (name "Net-(U$23-RX)") (class "Default")
      (node (ref "R16") (pin "1") (pinfunction "1_1") (pintype "passive"))
      (node (ref "U$23") (pin "3") (pinfunction "RX_3") (pintype "bidirectional"))
    )
    (net (code "59") (name "Net-(U$23-TX)") (class "Default")
      (node (ref "R15") (pin "1") (pinfunction "1_1") (pintype "passive"))
      (node (ref "U$23") (pin "2") (pinfunction "TX_2") (pintype "bidirectional"))
    )
    (net (code "60") (name "Net-(U$23-V3)") (class "Default")
      (node (ref "C14") (pin "1") (pinfunction "1_1") (pintype "passive"))
      (node (ref "U$23") (pin "4") (pinfunction "V3_4") (pintype "bidirectional"))
    )
    (net (code "61") (name "Net-(U$23-XI)") (class "Default")
      (node (ref "C23") (pin "1") (pinfunction "1_1") (pintype "passive"))
      (node (ref "Q2") (pin "1") (pinfunction "1_1") (pintype "passive"))
      (node (ref "U$23") (pin "7") (pinfunction "XI_7") (pintype "bidirectional"))
    )
    (net (code "62") (name "Net-(U$23-XO)") (class "Default")
      (node (ref "C24") (pin "1") (pinfunction "1_1") (pintype "passive"))
      (node (ref "Q2") (pin "2") (pinfunction "2_2") (pintype "passive"))
      (node (ref "U$23") (pin "8") (pinfunction "XO_8") (pintype "bidirectional"))
    )
    (net (code "63") (name "Net-(VREG-P4)") (class "Default")
      (node (ref "SJ1") (pin "2") (pinfunction "2_2") (pintype "passive"))
      (node (ref "VREG") (pin "4") (pinfunction "P4_4") (pintype "bidirectional"))
    )
    (net (code "64") (name "VBAT") (class "Default")
      (node (ref "BATTERY") (pin "2") (pinfunction "+_2") (pintype "passive"))
      (node (ref "C10") (pin "1") (pinfunction "1_1") (pintype "passive"))
      (node (ref "D2") (pin "A") (pinfunction "A_A") (pintype "passive"))
      (node (ref "R10") (pin "2") (pinfunction "2_2") (pintype "passive"))
      (node (ref "U$1") (pin "3") (pinfunction "VBAT_3") (pintype "power_in"))
    )
    (net (code "65") (name "VBUS") (class "Default")
      (node (ref "C1") (pin "1") (pinfunction "1_1") (pintype "passive"))
      (node (ref "C20") (pin "1") (pinfunction "1_1") (pintype "passive"))
      (node (ref "C21") (pin "1") (pinfunction "1_1") (pintype "passive"))
      (node (ref "C4") (pin "1") (pinfunction "1_1") (pintype "passive"))
      (node (ref "CHG_LED") (pin "A") (pinfunction "A_A") (pintype "passive"))
      (node (ref "D2") (pin "C") (pinfunction "C_C") (pintype "passive"))
      (node (ref "PWR") (pin "2") (pinfunction "P_2") (pintype "passive"))
      (node (ref "U$1") (pin "4") (pinfunction "VIN_4") (pintype "power_in"))
      (node (ref "U$23") (pin "16") (pinfunction "VCC_16") (pintype "bidirectional"))
      (node (ref "USB") (pin "VBUS") (pinfunction "VBUS_VBUS") (pintype "bidirectional"))
      (node (ref "VREG") (pin "1") (pinfunction "IN_1") (pintype "bidirectional"))
    )
    (net (code "66") (name "unconnected-(ESP32-CLK-Pad20)") (class "Default")
      (node (ref "ESP32") (pin "20") (pinfunction "CLK_20") (pintype "bidirectional"))
    )
    (net (code "67") (name "unconnected-(ESP32-CMD-Pad19)") (class "Default")
      (node (ref "ESP32") (pin "19") (pinfunction "CMD_19") (pintype "bidirectional"))
    )
    (net (code "68") (name "unconnected-(ESP32-NC-Pad27)") (class "Default")
      (node (ref "ESP32") (pin "27") (pinfunction "NC_27") (pintype "bidirectional"))
    )
    (net (code "69") (name "unconnected-(ESP32-NC-Pad28)") (class "Default")
      (node (ref "ESP32") (pin "28") (pinfunction "NC_28") (pintype "bidirectional"))
    )
    (net (code "70") (name "unconnected-(ESP32-NC-Pad32)") (class "Default")
      (node (ref "ESP32") (pin "32") (pinfunction "NC_32") (pintype "bidirectional"))
    )
    (net (code "71") (name "unconnected-(ESP32-SD0-Pad21)") (class "Default")
      (node (ref "ESP32") (pin "21") (pinfunction "SD0_21") (pintype "bidirectional"))
    )
    (net (code "72") (name "unconnected-(ESP32-SD1-Pad22)") (class "Default")
      (node (ref "ESP32") (pin "22") (pinfunction "SD1_22") (pintype "bidirectional"))
    )
    (net (code "73") (name "unconnected-(ESP32-SD2-Pad17)") (class "Default")
      (node (ref "ESP32") (pin "17") (pinfunction "SD2_17") (pintype "bidirectional"))
    )
    (net (code "74") (name "unconnected-(ESP32-SD3-Pad18)") (class "Default")
      (node (ref "ESP32") (pin "18") (pinfunction "SD3_18") (pintype "bidirectional"))
    )
    (net (code "75") (name "unconnected-(JACK-Pad2)") (class "Default")
      (node (ref "JACK") (pin "2") (pinfunction "2_2") (pintype "bidirectional"))
    )
    (net (code "76") (name "unconnected-(JACK-Pad4)") (class "Default")
      (node (ref "JACK") (pin "4") (pinfunction "4_4") (pintype "bidirectional"))
    )
    (net (code "77") (name "unconnected-(LCD-XL-PadP$15)") (class "Default")
      (node (ref "LCD") (pin "P$15") (pinfunction "XL_P$15") (pintype "bidirectional"))
    )
    (net (code "78") (name "unconnected-(LCD-XR-PadP$16)") (class "Default")
      (node (ref "LCD") (pin "P$16") (pinfunction "XR_P$16") (pintype "bidirectional"))
    )
    (net (code "79") (name "unconnected-(LCD-YD-PadP$17)") (class "Default")
      (node (ref "LCD") (pin "P$17") (pinfunction "YD_P$17") (pintype "bidirectional"))
    )
    (net (code "80") (name "unconnected-(LCD-YU-PadP$18)") (class "Default")
      (node (ref "LCD") (pin "P$18") (pinfunction "YU_P$18") (pintype "bidirectional"))
    )
    (net (code "81") (name "unconnected-(PWR-S-Pad3)") (class "Default")
      (node (ref "PWR") (pin "3") (pinfunction "S_3") (pintype "passive"))
    )
    (net (code "82") (name "unconnected-(SD_CARD-PadCD)") (class "Default")
      (node (ref "SD_CARD") (pin "CD") (pinfunction "CD_CD") (pintype "bidirectional"))
    )
    (net (code "83") (name "unconnected-(SD_CARD-PadDAT1)") (class "Default")
      (node (ref "SD_CARD") (pin "DAT1") (pinfunction "DAT1_DAT1") (pintype "bidirectional"))
    )
    (net (code "84") (name "unconnected-(SD_CARD-PadDAT2)") (class "Default")
      (node (ref "SD_CARD") (pin "DAT2") (pinfunction "DAT2_DAT2") (pintype "bidirectional"))
    )
    (net (code "85") (name "unconnected-(U$23-CTS-Pad9)") (class "Default")
      (node (ref "U$23") (pin "9") (pinfunction "CTS_9") (pintype "bidirectional"))
    )
    (net (code "86") (name "unconnected-(U$23-DCD-Pad12)") (class "Default")
      (node (ref "U$23") (pin "12") (pinfunction "DCD_12") (pintype "bidirectional"))
    )
    (net (code "87") (name "unconnected-(U$23-DSR-Pad10)") (class "Default")
      (node (ref "U$23") (pin "10") (pinfunction "DSR_10") (pintype "bidirectional"))
    )
    (net (code "88") (name "unconnected-(U$23-RI-Pad11)") (class "Default")
      (node (ref "U$23") (pin "11") (pinfunction "RI_11") (pintype "bidirectional"))
    )
    (net (code "89") (name "unconnected-(U$23-RS232-Pad15)") (class "Default")
      (node (ref "U$23") (pin "15") (pinfunction "RS232_15") (pintype "bidirectional"))
    )
  )
)
